# ADC.net
KiCad netlist of a schematic drawn in Altium Designer
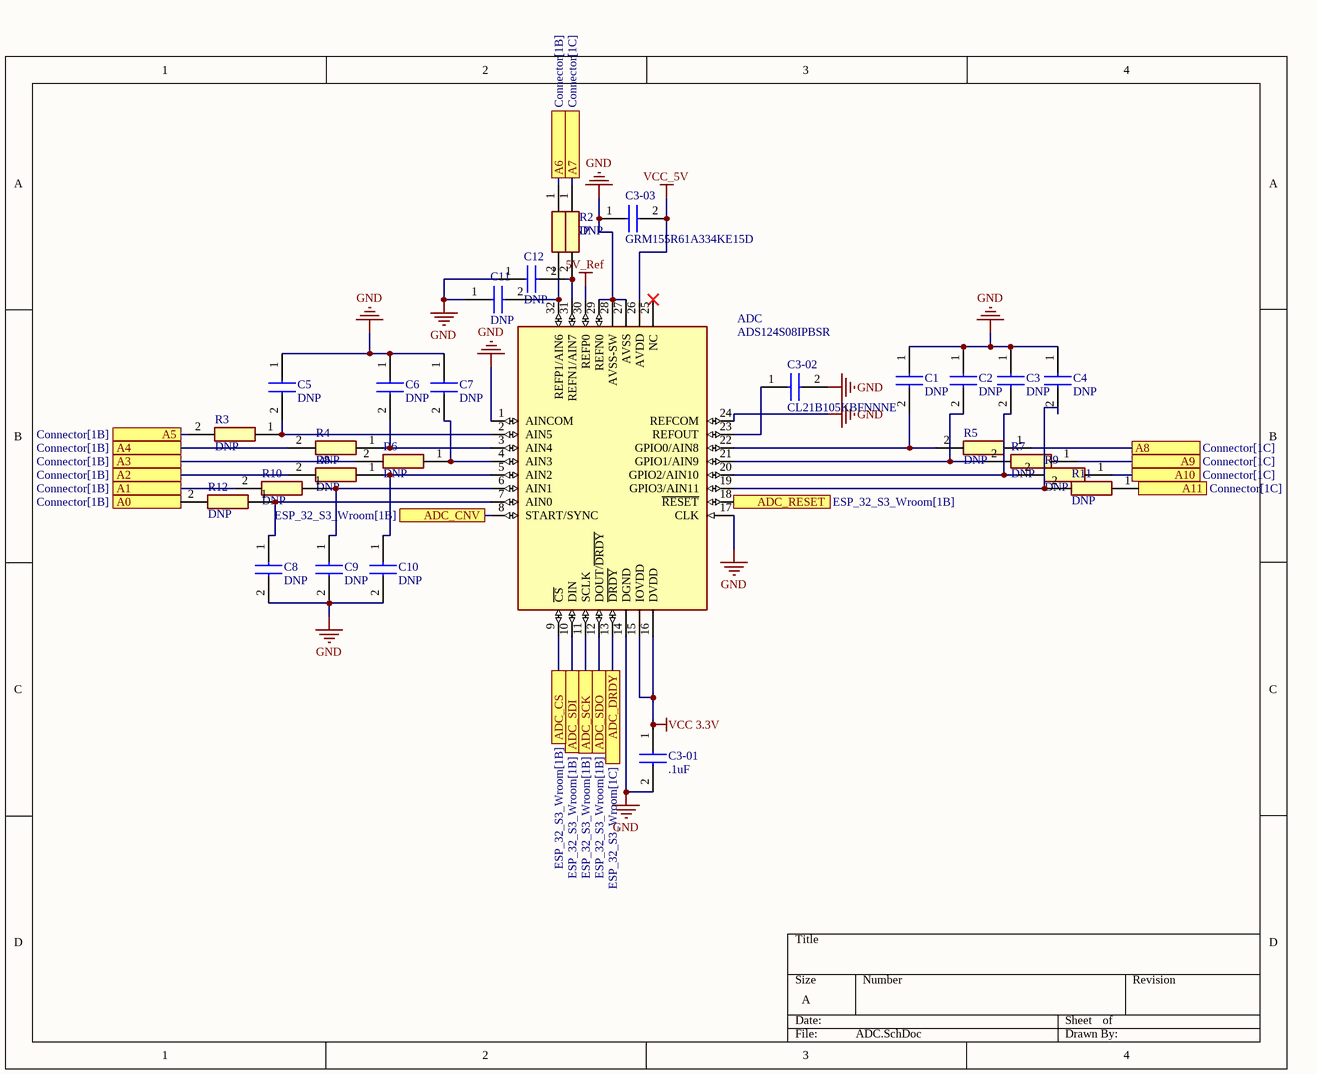
[diagram p0: ADC.SchDoc]

(export (version "E")
  (design (tool "Eeschema 10.0.6"))
  (components
    (comp (ref "ADC")
      (value "ADS124S08IPBSR")
      (footprint "SamacSys:QFP50P700X700X120-32N")
      (description "Integrated Circuit")
      (fields (field (name "MOUSER PART NUMBER") "595-ADS124S08IPBSR"))
      (libsource (lib "*") (part "ADS124S08IPBSR"))
    )
    (comp (ref "C1")
      (value "DNP")
      (footprint "SamacSys:C0402C104J4RACTU")
      (description "Capacitor")
      (fields
        (field (name "MANUFACTURER_PART_NUMBER") "C0402C105K9PACTU")
        (field (name "MOUSER PART NUMBER") "80-C0402C105K9P")
      )
      (libsource (lib "*") (part "C0402C105K9PACTU"))
    )
    (comp (ref "C2")
      (value "DNP")
      (footprint "SamacSys:C0402C104J4RACTU")
      (description "Capacitor")
      (fields
        (field (name "MANUFACTURER_PART_NUMBER") "C0402C105K9PACTU")
        (field (name "MOUSER PART NUMBER") "80-C0402C105K9P")
      )
      (libsource (lib "*") (part "C0402C105K9PACTU"))
    )
    (comp (ref "C3")
      (value "DNP")
      (footprint "SamacSys:C0402C104J4RACTU")
      (description "Capacitor")
      (fields
        (field (name "MANUFACTURER_PART_NUMBER") "C0402C105K9PACTU")
        (field (name "MOUSER PART NUMBER") "80-C0402C105K9P")
      )
      (libsource (lib "*") (part "C0402C105K9PACTU"))
    )
    (comp (ref "C3-01")
      (value ".1uF")
      (footprint "SamacSys:CAPC2012X95N")
      (description "Capacitor")
      (fields
        (field (name "MANUFACTURER_PART_NUMBER") "CL21B104KBCNNNC")
        (field (name "MOUSER PART NUMBER") "187-CL21B104KBCNNNC")
      )
      (libsource (lib "*") (part "CL21B104KBCNNNC"))
    )
    (comp (ref "C3-02")
      (value "CL21B105KBFNNNE")
      (footprint "SamacSys:CAPC2012X135N")
      (description "Capacitor")
      (fields (field (name "MOUSER PART NUMBER") "187-CL21B105KBFNNNE"))
      (libsource (lib "*") (part "CL21B105KBFNNNE"))
    )
    (comp (ref "C3-03")
      (value "GRM155R61A334KE15D")
      (footprint "SamacSys:CAPC1005X70N")
      (description "Capacitor")
      (fields (field (name "MOUSER PART NUMBER") "81-GRM155R61A334KE5D"))
      (libsource (lib "*") (part "GRM155R61A334KE15D"))
    )
    (comp (ref "C4")
      (value "DNP")
      (footprint "SamacSys:C0402C104J4RACTU")
      (description "Capacitor")
      (fields
        (field (name "MANUFACTURER_PART_NUMBER") "C0402C105K9PACTU")
        (field (name "MOUSER PART NUMBER") "80-C0402C105K9P")
      )
      (libsource (lib "*") (part "C0402C105K9PACTU"))
    )
    (comp (ref "C5")
      (value "DNP")
      (footprint "SamacSys:C0402C104J4RACTU")
      (description "Capacitor")
      (fields
        (field (name "MANUFACTURER_PART_NUMBER") "C0402C105K9PACTU")
        (field (name "MOUSER PART NUMBER") "80-C0402C105K9P")
      )
      (libsource (lib "*") (part "C0402C105K9PACTU"))
    )
    (comp (ref "C6")
      (value "DNP")
      (footprint "SamacSys:C0402C104J4RACTU")
      (description "Capacitor")
      (fields
        (field (name "MANUFACTURER_PART_NUMBER") "C0402C105K9PACTU")
        (field (name "MOUSER PART NUMBER") "80-C0402C105K9P")
      )
      (libsource (lib "*") (part "C0402C105K9PACTU"))
    )
    (comp (ref "C7")
      (value "DNP")
      (footprint "SamacSys:C0402C104J4RACTU")
      (description "Capacitor")
      (fields
        (field (name "MANUFACTURER_PART_NUMBER") "C0402C105K9PACTU")
        (field (name "MOUSER PART NUMBER") "80-C0402C105K9P")
      )
      (libsource (lib "*") (part "C0402C105K9PACTU"))
    )
    (comp (ref "C8")
      (value "DNP")
      (footprint "SamacSys:C0402C104J4RACTU")
      (description "Capacitor")
      (fields
        (field (name "MANUFACTURER_PART_NUMBER") "C0402C105K9PACTU")
        (field (name "MOUSER PART NUMBER") "80-C0402C105K9P")
      )
      (libsource (lib "*") (part "C0402C105K9PACTU"))
    )
    (comp (ref "C9")
      (value "DNP")
      (footprint "SamacSys:C0402C104J4RACTU")
      (description "Capacitor")
      (fields
        (field (name "MANUFACTURER_PART_NUMBER") "C0402C105K9PACTU")
        (field (name "MOUSER PART NUMBER") "80-C0402C105K9P")
      )
      (libsource (lib "*") (part "C0402C105K9PACTU"))
    )
    (comp (ref "C10")
      (value "DNP")
      (footprint "SamacSys:C0402C104J4RACTU")
      (description "Capacitor")
      (fields
        (field (name "MANUFACTURER_PART_NUMBER") "C0402C105K9PACTU")
        (field (name "MOUSER PART NUMBER") "80-C0402C105K9P")
      )
      (libsource (lib "*") (part "C0402C105K9PACTU"))
    )
    (comp (ref "C11")
      (value "DNP")
      (footprint "SamacSys:C0402C104J4RACTU")
      (description "Capacitor")
      (fields
        (field (name "MANUFACTURER_PART_NUMBER") "C0402C105K9PACTU")
        (field (name "MOUSER PART NUMBER") "80-C0402C105K9P")
      )
      (libsource (lib "*") (part "C0402C105K9PACTU"))
    )
    (comp (ref "C12")
      (value "DNP")
      (footprint "SamacSys:C0402C104J4RACTU")
      (description "Capacitor")
      (fields
        (field (name "MANUFACTURER_PART_NUMBER") "C0402C105K9PACTU")
        (field (name "MOUSER PART NUMBER") "80-C0402C105K9P")
      )
      (libsource (lib "*") (part "C0402C105K9PACTU"))
    )
    (comp (ref "R1")
      (value "DNP")
      (footprint "SamacSys:RESC1005X40N")
      (description "Resistor")
      (fields
        (field (name "MANUFACTURER_PART_NUMBER") "RC0402FR-071KL")
        (field (name "MOUSER PART NUMBER") "603-RC0402FR-071KL")
      )
      (libsource (lib "*") (part "RC0402FR-071KL"))
    )
    (comp (ref "R2")
      (value "DNP")
      (footprint "SamacSys:RESC1005X40N")
      (description "Resistor")
      (fields
        (field (name "MANUFACTURER_PART_NUMBER") "RC0402FR-071KL")
        (field (name "MOUSER PART NUMBER") "603-RC0402FR-071KL")
      )
      (libsource (lib "*") (part "RC0402FR-071KL"))
    )
    (comp (ref "R3")
      (value "DNP")
      (footprint "SamacSys:RESC1005X40N")
      (description "Resistor")
      (fields
        (field (name "MANUFACTURER_PART_NUMBER") "RC0402FR-071KL")
        (field (name "MOUSER PART NUMBER") "603-RC0402FR-071KL")
      )
      (libsource (lib "") (part "RC0402FR-071KL_1"))
    )
    (comp (ref "R4")
      (value "DNP")
      (footprint "SamacSys:RESC1005X40N")
      (description "Resistor")
      (fields
        (field (name "MANUFACTURER_PART_NUMBER") "RC0402FR-071KL")
        (field (name "MOUSER PART NUMBER") "603-RC0402FR-071KL")
      )
      (libsource (lib "") (part "RC0402FR-071KL_1"))
    )
    (comp (ref "R5")
      (value "DNP")
      (footprint "SamacSys:RESC1005X40N")
      (description "Resistor")
      (fields
        (field (name "MANUFACTURER_PART_NUMBER") "RC0402FR-071KL")
        (field (name "MOUSER PART NUMBER") "603-RC0402FR-071KL")
      )
      (libsource (lib "") (part "RC0402FR-071KL_1"))
    )
    (comp (ref "R6")
      (value "DNP")
      (footprint "SamacSys:RESC1005X40N")
      (description "Resistor")
      (fields
        (field (name "MANUFACTURER_PART_NUMBER") "RC0402FR-071KL")
        (field (name "MOUSER PART NUMBER") "603-RC0402FR-071KL")
      )
      (libsource (lib "") (part "RC0402FR-071KL_1"))
    )
    (comp (ref "R7")
      (value "DNP")
      (footprint "SamacSys:RESC1005X40N")
      (description "Resistor")
      (fields
        (field (name "MANUFACTURER_PART_NUMBER") "RC0402FR-071KL")
        (field (name "MOUSER PART NUMBER") "603-RC0402FR-071KL")
      )
      (libsource (lib "") (part "RC0402FR-071KL_1"))
    )
    (comp (ref "R8")
      (value "DNP")
      (footprint "SamacSys:RESC1005X40N")
      (description "Resistor")
      (fields
        (field (name "MANUFACTURER_PART_NUMBER") "RC0402FR-071KL")
        (field (name "MOUSER PART NUMBER") "603-RC0402FR-071KL")
      )
      (libsource (lib "") (part "RC0402FR-071KL_1"))
    )
    (comp (ref "R9")
      (value "DNP")
      (footprint "SamacSys:RESC1005X40N")
      (description "Resistor")
      (fields
        (field (name "MANUFACTURER_PART_NUMBER") "RC0402FR-071KL")
        (field (name "MOUSER PART NUMBER") "603-RC0402FR-071KL")
      )
      (libsource (lib "") (part "RC0402FR-071KL_1"))
    )
    (comp (ref "R10")
      (value "DNP")
      (footprint "SamacSys:RESC1005X40N")
      (description "Resistor")
      (fields
        (field (name "MANUFACTURER_PART_NUMBER") "RC0402FR-071KL")
        (field (name "MOUSER PART NUMBER") "603-RC0402FR-071KL")
      )
      (libsource (lib "") (part "RC0402FR-071KL_1"))
    )
    (comp (ref "R11")
      (value "DNP")
      (footprint "SamacSys:RESC1005X40N")
      (description "Resistor")
      (fields
        (field (name "MANUFACTURER_PART_NUMBER") "RC0402FR-071KL")
        (field (name "MOUSER PART NUMBER") "603-RC0402FR-071KL")
      )
      (libsource (lib "") (part "RC0402FR-071KL_1"))
    )
    (comp (ref "R12")
      (value "DNP")
      (footprint "SamacSys:RESC1005X40N")
      (description "Resistor")
      (fields
        (field (name "MANUFACTURER_PART_NUMBER") "RC0402FR-071KL")
        (field (name "MOUSER PART NUMBER") "603-RC0402FR-071KL")
      )
      (libsource (lib "") (part "RC0402FR-071KL_1"))
    )
  )
  (nets
    (net (code "1") (name "/A0") (class "Default")
      (node (ref "R12") (pin "2") (pinfunction "2_2") (pintype "passive"))
    )
    (net (code "2") (name "/A1") (class "Default")
      (node (ref "R10") (pin "2") (pinfunction "2_2") (pintype "passive"))
    )
    (net (code "3") (name "/A2") (class "Default")
      (node (ref "R8") (pin "2") (pinfunction "2_2") (pintype "passive"))
    )
    (net (code "4") (name "/A3") (class "Default")
      (node (ref "R6") (pin "2") (pinfunction "2_2") (pintype "passive"))
    )
    (net (code "5") (name "/A4") (class "Default")
      (node (ref "R4") (pin "2") (pinfunction "2_2") (pintype "passive"))
    )
    (net (code "6") (name "/A5") (class "Default")
      (node (ref "R3") (pin "2") (pinfunction "2_2") (pintype "passive"))
    )
    (net (code "7") (name "/A6") (class "Default")
      (node (ref "R1") (pin "1") (pinfunction "1_1") (pintype "passive"))
    )
    (net (code "8") (name "/A7") (class "Default")
      (node (ref "R2") (pin "1") (pinfunction "1_1") (pintype "passive"))
    )
    (net (code "9") (name "/A8") (class "Default")
      (node (ref "R5") (pin "1") (pinfunction "1_1") (pintype "passive"))
    )
    (net (code "10") (name "/A9") (class "Default")
      (node (ref "R7") (pin "1") (pinfunction "1_1") (pintype "passive"))
    )
    (net (code "11") (name "/A10") (class "Default")
      (node (ref "R9") (pin "1") (pinfunction "1_1") (pintype "passive"))
    )
    (net (code "12") (name "/A11") (class "Default")
      (node (ref "R11") (pin "1") (pinfunction "1_1") (pintype "passive"))
    )
    (net (code "13") (name "/ADC_CNV") (class "Default")
      (node (ref "ADC") (pin "8") (pinfunction "START/SYNC_8") (pintype "bidirectional"))
    )
    (net (code "14") (name "/ADC_CS") (class "Default")
      (node (ref "ADC") (pin "9") (pinfunction "~{CS}_9") (pintype "bidirectional"))
    )
    (net (code "15") (name "/ADC_DRDY") (class "Default")
      (node (ref "ADC") (pin "13") (pinfunction "~{DRDY}_13") (pintype "bidirectional"))
    )
    (net (code "16") (name "/ADC_RESET") (class "Default")
      (node (ref "ADC") (pin "18") (pinfunction "~{RESET}_18") (pintype "bidirectional"))
    )
    (net (code "17") (name "/ADC_SCK") (class "Default")
      (node (ref "ADC") (pin "11") (pinfunction "SCLK_11") (pintype "bidirectional"))
    )
    (net (code "18") (name "/ADC_SDI") (class "Default")
      (node (ref "ADC") (pin "10") (pinfunction "DIN_10") (pintype "bidirectional"))
    )
    (net (code "19") (name "/ADC_SDO") (class "Default")
      (node (ref "ADC") (pin "12") (pinfunction "DOUT/~{DRDY}_12") (pintype "bidirectional"))
    )
    (net (code "20") (name "5V_Ref") (class "Default")
      (node (ref "ADC") (pin "30") (pinfunction "REFP0_30") (pintype "bidirectional"))
    )
    (net (code "21") (name "GND") (class "Default")
      (node (ref "ADC") (pin "1") (pinfunction "AINCOM_1") (pintype "bidirectional"))
      (node (ref "ADC") (pin "14") (pinfunction "DGND_14") (pintype "power_in"))
      (node (ref "ADC") (pin "17") (pinfunction "CLK_17") (pintype "input"))
      (node (ref "ADC") (pin "24") (pinfunction "REFCOM_24") (pintype "bidirectional"))
      (node (ref "ADC") (pin "27") (pinfunction "AVSS_27") (pintype "power_in"))
      (node (ref "ADC") (pin "28") (pinfunction "AVSS-SW_28") (pintype "power_in"))
      (node (ref "ADC") (pin "29") (pinfunction "REFN0_29") (pintype "bidirectional"))
      (node (ref "C1") (pin "1") (pinfunction "1_1") (pintype "passive"))
      (node (ref "C10") (pin "2") (pinfunction "2_2") (pintype "passive"))
      (node (ref "C11") (pin "1") (pinfunction "1_1") (pintype "passive"))
      (node (ref "C12") (pin "1") (pinfunction "1_1") (pintype "passive"))
      (node (ref "C2") (pin "1") (pinfunction "1_1") (pintype "passive"))
      (node (ref "C3") (pin "1") (pinfunction "1_1") (pintype "passive"))
      (node (ref "C3-01") (pin "2") (pinfunction "2_2") (pintype "passive"))
      (node (ref "C3-02") (pin "2") (pinfunction "2_2") (pintype "passive"))
      (node (ref "C3-03") (pin "1") (pinfunction "1_1") (pintype "passive"))
      (node (ref "C4") (pin "1") (pinfunction "1_1") (pintype "passive"))
      (node (ref "C5") (pin "1") (pinfunction "1_1") (pintype "passive"))
      (node (ref "C6") (pin "1") (pinfunction "1_1") (pintype "passive"))
      (node (ref "C7") (pin "1") (pinfunction "1_1") (pintype "passive"))
      (node (ref "C8") (pin "2") (pinfunction "2_2") (pintype "passive"))
      (node (ref "C9") (pin "2") (pinfunction "2_2") (pintype "passive"))
    )
    (net (code "22") (name "Net-(ADC-AIN0)") (class "Default")
      (node (ref "ADC") (pin "7") (pinfunction "AIN0_7") (pintype "bidirectional"))
      (node (ref "C8") (pin "1") (pinfunction "1_1") (pintype "passive"))
      (node (ref "R12") (pin "1") (pinfunction "1_1") (pintype "passive"))
    )
    (net (code "23") (name "Net-(ADC-AIN1)") (class "Default")
      (node (ref "ADC") (pin "6") (pinfunction "AIN1_6") (pintype "bidirectional"))
      (node (ref "C9") (pin "1") (pinfunction "1_1") (pintype "passive"))
      (node (ref "R10") (pin "1") (pinfunction "1_1") (pintype "passive"))
    )
    (net (code "24") (name "Net-(ADC-AIN2)") (class "Default")
      (node (ref "ADC") (pin "5") (pinfunction "AIN2_5") (pintype "bidirectional"))
      (node (ref "C10") (pin "1") (pinfunction "1_1") (pintype "passive"))
      (node (ref "R8") (pin "1") (pinfunction "1_1") (pintype "passive"))
    )
    (net (code "25") (name "Net-(ADC-AIN3)") (class "Default")
      (node (ref "ADC") (pin "4") (pinfunction "AIN3_4") (pintype "bidirectional"))
      (node (ref "C7") (pin "2") (pinfunction "2_2") (pintype "passive"))
      (node (ref "R6") (pin "1") (pinfunction "1_1") (pintype "passive"))
    )
    (net (code "26") (name "Net-(ADC-AIN4)") (class "Default")
      (node (ref "ADC") (pin "3") (pinfunction "AIN4_3") (pintype "bidirectional"))
      (node (ref "C6") (pin "2") (pinfunction "2_2") (pintype "passive"))
      (node (ref "R4") (pin "1") (pinfunction "1_1") (pintype "passive"))
    )
    (net (code "27") (name "Net-(ADC-AIN5)") (class "Default")
      (node (ref "ADC") (pin "2") (pinfunction "AIN5_2") (pintype "bidirectional"))
      (node (ref "C5") (pin "2") (pinfunction "2_2") (pintype "passive"))
      (node (ref "R3") (pin "1") (pinfunction "1_1") (pintype "passive"))
    )
    (net (code "28") (name "Net-(ADC-GPIO0{slash}AIN8)") (class "Default")
      (node (ref "ADC") (pin "22") (pinfunction "GPIO0/AIN8_22") (pintype "bidirectional"))
      (node (ref "C1") (pin "2") (pinfunction "2_2") (pintype "passive"))
      (node (ref "R5") (pin "2") (pinfunction "2_2") (pintype "passive"))
    )
    (net (code "29") (name "Net-(ADC-GPIO1{slash}AIN9)") (class "Default")
      (node (ref "ADC") (pin "21") (pinfunction "GPIO1/AIN9_21") (pintype "bidirectional"))
      (node (ref "C2") (pin "2") (pinfunction "2_2") (pintype "passive"))
      (node (ref "R7") (pin "2") (pinfunction "2_2") (pintype "passive"))
    )
    (net (code "30") (name "Net-(ADC-GPIO2{slash}AIN10)") (class "Default")
      (node (ref "ADC") (pin "20") (pinfunction "GPIO2/AIN10_20") (pintype "bidirectional"))
      (node (ref "C3") (pin "2") (pinfunction "2_2") (pintype "passive"))
      (node (ref "R9") (pin "2") (pinfunction "2_2") (pintype "passive"))
    )
    (net (code "31") (name "Net-(ADC-GPIO3{slash}AIN11)") (class "Default")
      (node (ref "ADC") (pin "19") (pinfunction "GPIO3/AIN11_19") (pintype "bidirectional"))
      (node (ref "C4") (pin "2") (pinfunction "2_2") (pintype "passive"))
      (node (ref "R11") (pin "2") (pinfunction "2_2") (pintype "passive"))
    )
    (net (code "32") (name "Net-(ADC-REFN1{slash}AIN7)") (class "Default")
      (node (ref "ADC") (pin "31") (pinfunction "REFN1/AIN7_31") (pintype "bidirectional"))
      (node (ref "C12") (pin "2") (pinfunction "2_2") (pintype "passive"))
      (node (ref "R2") (pin "2") (pinfunction "2_2") (pintype "passive"))
    )
    (net (code "33") (name "Net-(ADC-REFOUT)") (class "Default")
      (node (ref "ADC") (pin "23") (pinfunction "REFOUT_23") (pintype "bidirectional"))
      (node (ref "C3-02") (pin "1") (pinfunction "1_1") (pintype "passive"))
    )
    (net (code "34") (name "Net-(ADC-REFP1{slash}AIN6)") (class "Default")
      (node (ref "ADC") (pin "32") (pinfunction "REFP1/AIN6_32") (pintype "bidirectional"))
      (node (ref "C11") (pin "2") (pinfunction "2_2") (pintype "passive"))
      (node (ref "R1") (pin "2") (pinfunction "2_2") (pintype "passive"))
    )
    (net (code "35") (name "VCC 3.3V") (class "Default")
      (node (ref "ADC") (pin "15") (pinfunction "IOVDD_15") (pintype "power_in"))
      (node (ref "ADC") (pin "16") (pinfunction "DVDD_16") (pintype "power_in"))
      (node (ref "C3-01") (pin "1") (pinfunction "1_1") (pintype "passive"))
    )
    (net (code "36") (name "VCC_5V") (class "Default")
      (node (ref "ADC") (pin "26") (pinfunction "AVDD_26") (pintype "power_in"))
      (node (ref "C3-03") (pin "2") (pinfunction "2_2") (pintype "passive"))
    )
    (net (code "37") (name "unconnected-(ADC-NC-Pad25)") (class "Default")
      (node (ref "ADC") (pin "25") (pinfunction "NC_25") (pintype "passive+no_connect"))
    )
  )
)
